# MotorS_r_c.net
KiCad netlist of a schematic drawn in EAGLE
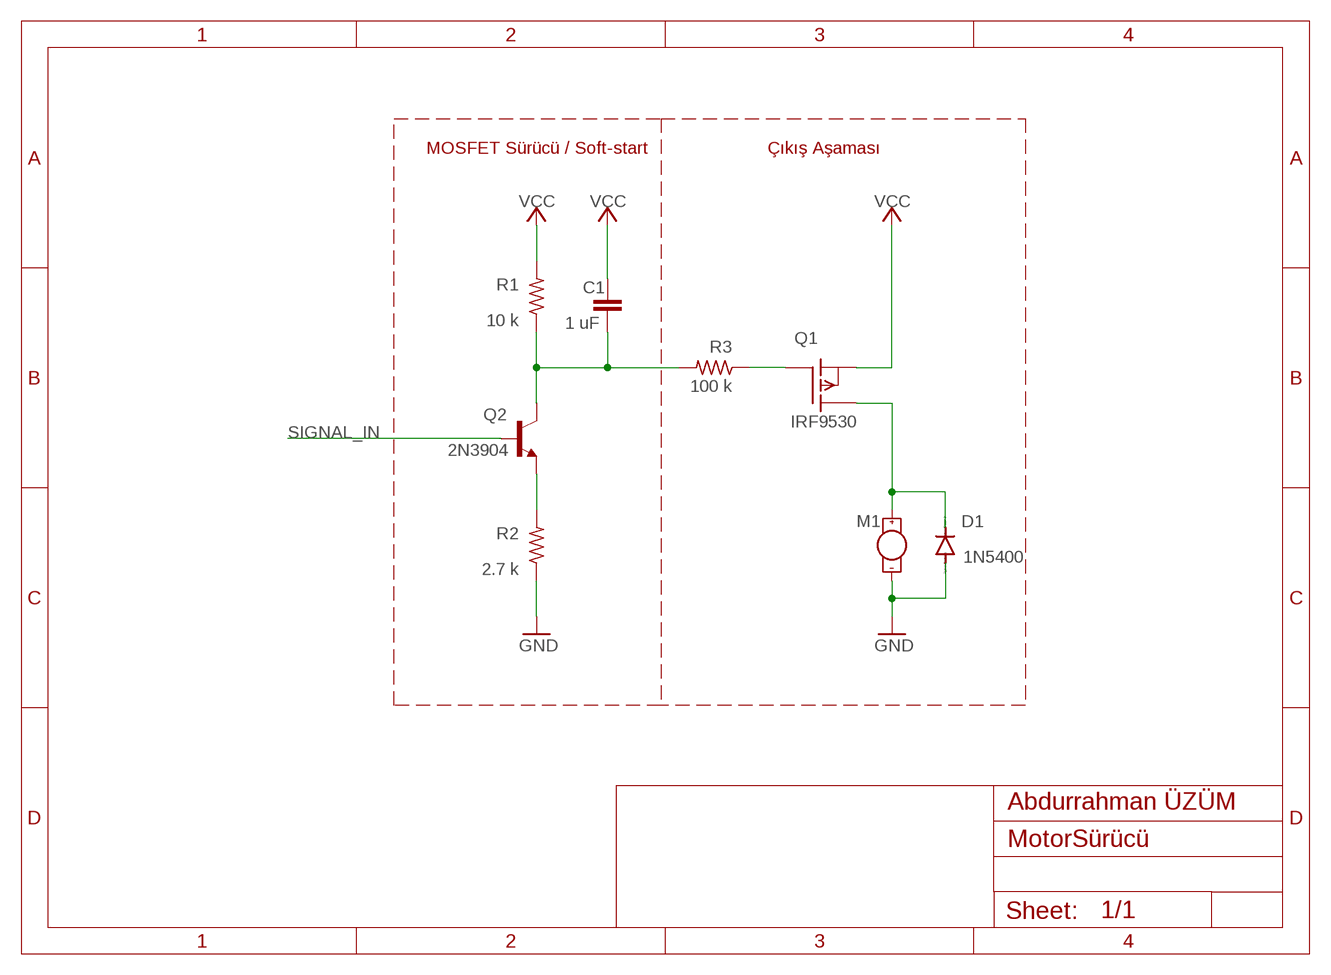
[diagram p0: schematic, sheet 1]

(export (version "E")
  (design (tool "Eeschema 10.0.6"))
  (components
    (comp (ref "C1")
      (value "1 uF")
      (footprint "eagle-import:C025-025X050")
      (libsource (lib "eagle-import") (part "C-EU025-025X050"))
    )
    (comp (ref "D1")
      (value "1N5400")
      (footprint "eagle-import:DO201-15")
      (libsource (lib "eagle-import") (part "1N5400"))
    )
    (comp (ref "M1")
      (value "MOTOR10MM")
      (footprint "eagle-import:VIBE-MOTOR-10MM")
      (libsource (lib "eagle-import") (part "MOTOR10MM"))
    )
    (comp (ref "Q1")
      (value "IRF9530")
      (footprint "eagle-import:TO220")
      (libsource (lib "eagle-import") (part "IRF9530"))
    )
    (comp (ref "Q2")
      (value "2N3904")
      (footprint "eagle-import:TO92")
      (libsource (lib "eagle-import") (part "2N3904"))
    )
    (comp (ref "R1")
      (value "10 k")
      (footprint "eagle-import:0204_7")
      (libsource (lib "eagle-import") (part "R-US_0204/7"))
    )
    (comp (ref "R2")
      (value "2.7 k")
      (footprint "eagle-import:0204_7")
      (libsource (lib "eagle-import") (part "R-US_0204/7"))
    )
    (comp (ref "R3")
      (value "100 k")
      (footprint "eagle-import:0204_7")
      (libsource (lib "eagle-import") (part "R-US_0204/7"))
    )
  )
  (nets
    (net (code "1") (name "/SIGNAL_IN") (class "Default")
      (node (ref "Q2") (pin "2") (pinfunction "B_2") (pintype "passive"))
    )
    (net (code "2") (name "GND") (class "Default")
      (node (ref "D1") (pin "A") (pinfunction "A_A") (pintype "passive"))
      (node (ref "M1") (pin "-") (pinfunction "-_-") (pintype "bidirectional"))
      (node (ref "R2") (pin "1") (pinfunction "1_1") (pintype "passive"))
    )
    (net (code "3") (name "Net-(Q1-D)") (class "Default")
      (node (ref "D1") (pin "C") (pinfunction "C_C") (pintype "passive"))
      (node (ref "M1") (pin "+") (pinfunction "+_+") (pintype "bidirectional"))
      (node (ref "Q1") (pin "2") (pinfunction "D_2") (pintype "passive"))
    )
    (net (code "4") (name "Net-(Q1-G)") (class "Default")
      (node (ref "Q1") (pin "1") (pinfunction "G_1") (pintype "passive"))
      (node (ref "R3") (pin "1") (pinfunction "1_1") (pintype "passive"))
    )
    (net (code "5") (name "Net-(Q2-C)") (class "Default")
      (node (ref "C1") (pin "2") (pinfunction "2_2") (pintype "passive"))
      (node (ref "Q2") (pin "1") (pinfunction "C_1") (pintype "passive"))
      (node (ref "R1") (pin "1") (pinfunction "1_1") (pintype "passive"))
      (node (ref "R3") (pin "2") (pinfunction "2_2") (pintype "passive"))
    )
    (net (code "6") (name "Net-(Q2-E)") (class "Default")
      (node (ref "Q2") (pin "3") (pinfunction "E_3") (pintype "passive"))
      (node (ref "R2") (pin "2") (pinfunction "2_2") (pintype "passive"))
    )
    (net (code "7") (name "VCC") (class "Default")
      (node (ref "C1") (pin "1") (pinfunction "1_1") (pintype "passive"))
      (node (ref "Q1") (pin "3") (pinfunction "S_3") (pintype "passive"))
      (node (ref "R1") (pin "2") (pinfunction "2_2") (pintype "passive"))
    )
  )
)
